# SAMC21_Xplained_Pro_Peripherals.net
KiCad netlist of a schematic drawn in Altium Designer
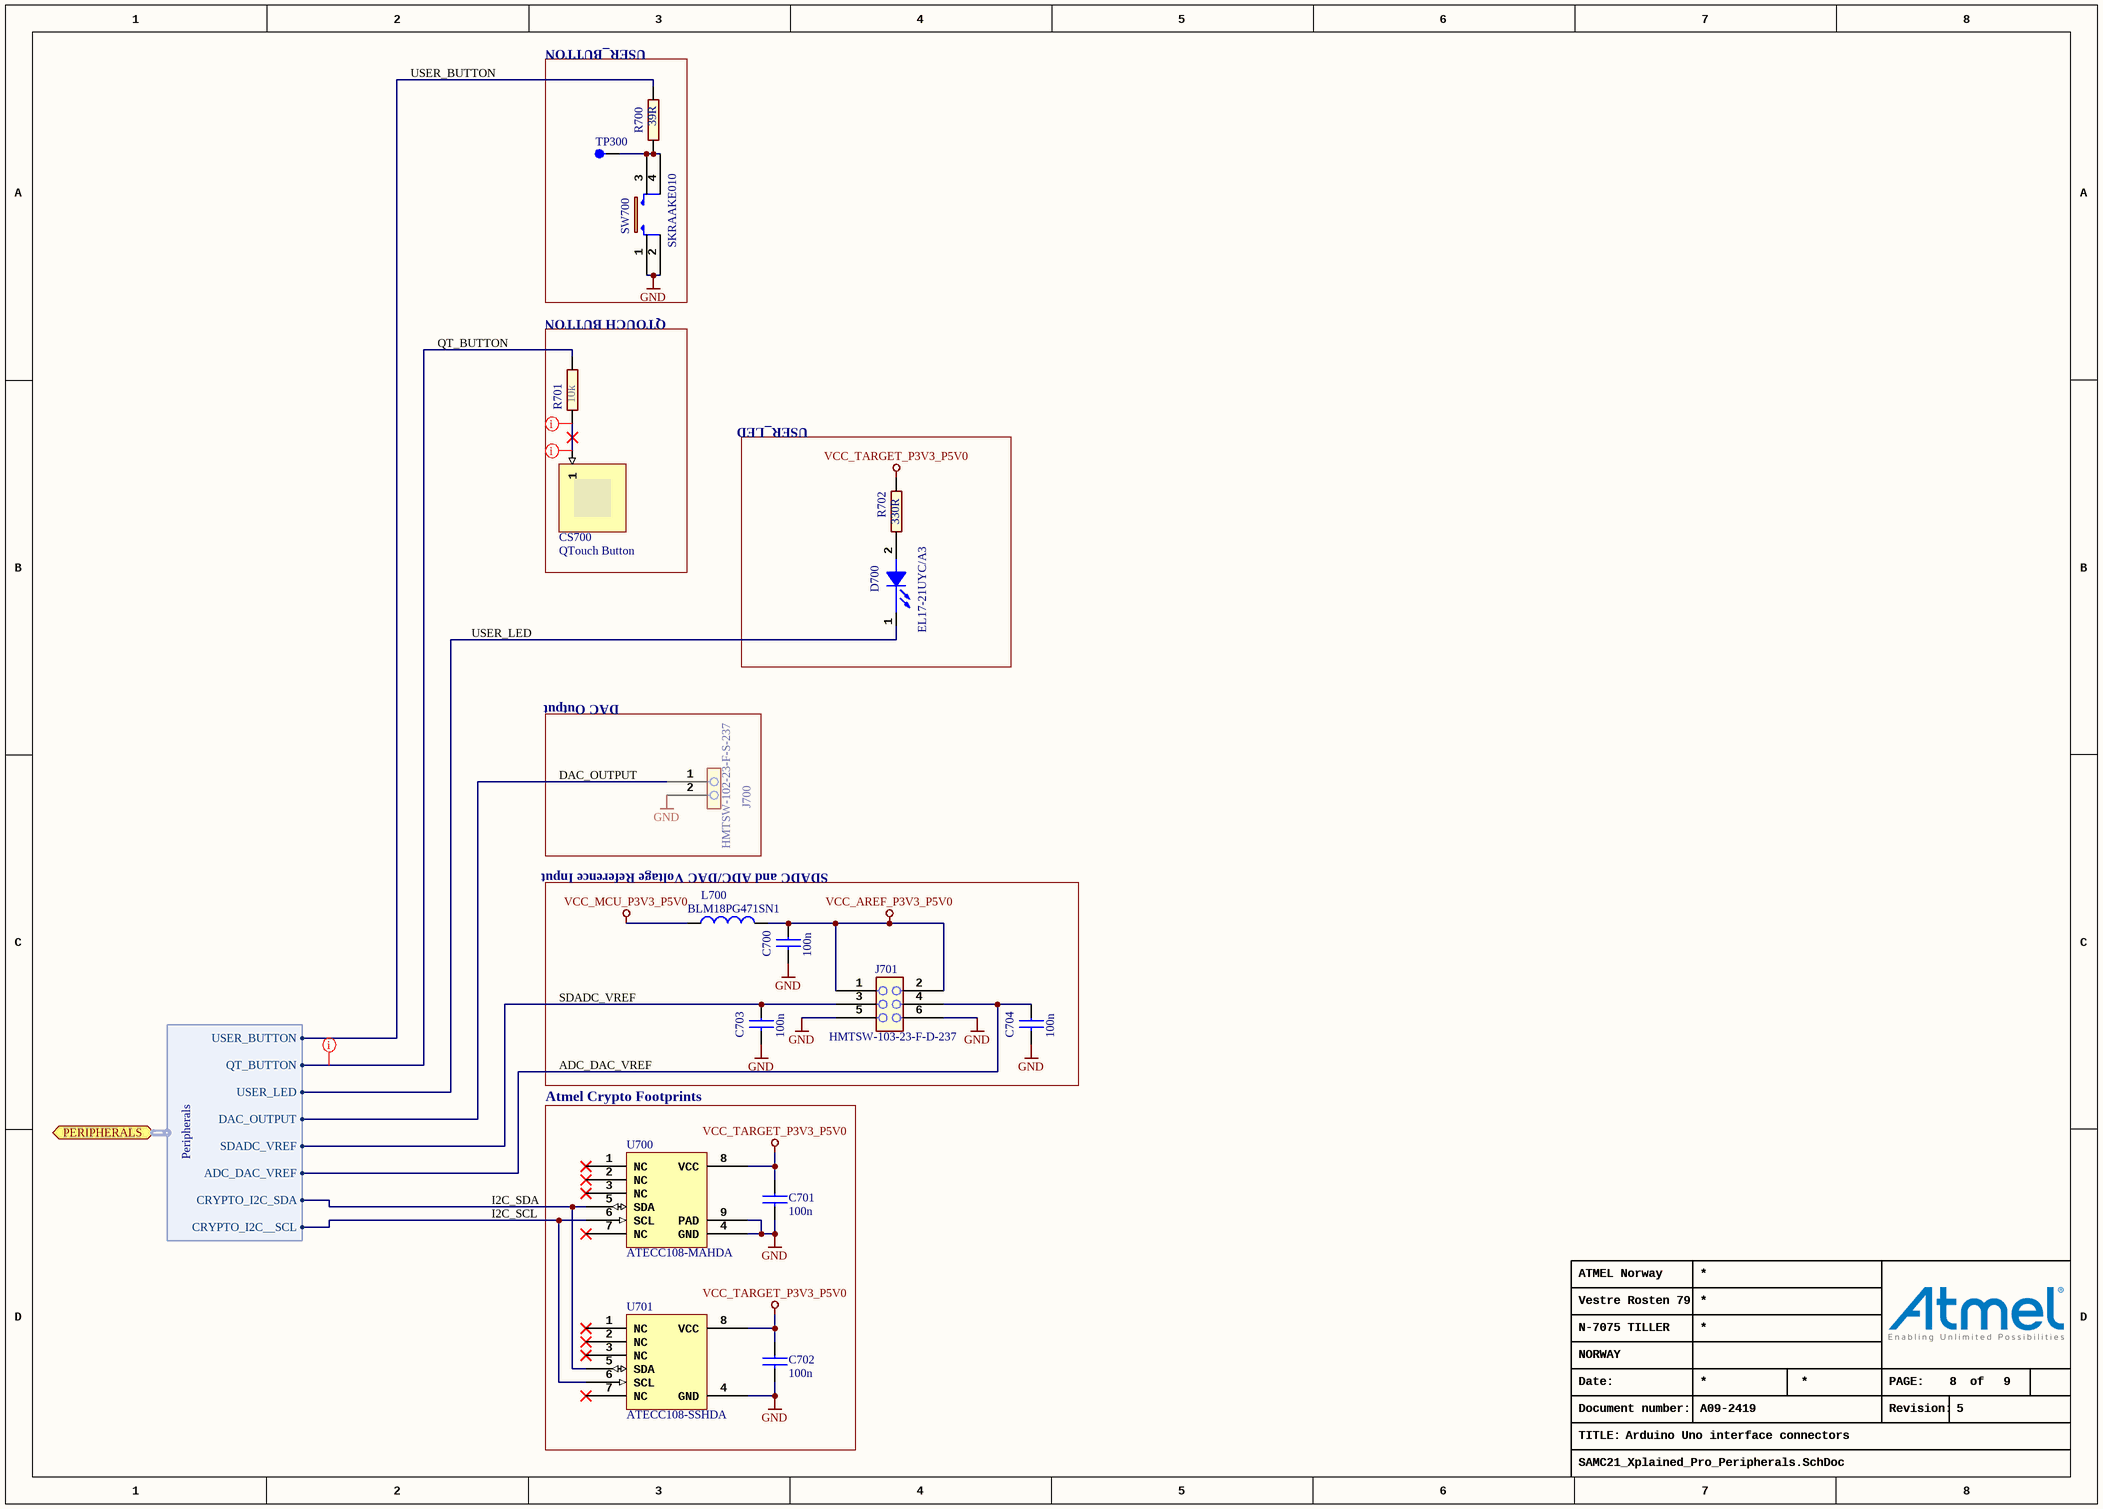
[diagram p0: SAMC21_Xplained_Pro_Peripherals.SchDoc]

(export (version "E")
  (design (tool "Eeschema 10.0.6"))
  (components
    (comp (ref "C700")
      (value "100n")
      (footprint "AP1-00001")
      (description "Ceramic capacitor, SMD 0402, X7R, 16V, +/-10%")
      (fields (field (name "TOLERANCE") "16V, +/-10%") (field (name "MANUFACTURER") "Kemet"))
      (libsource (lib "AltiumDbLib") (part "CAP-NONPOL"))
    )
    (comp (ref "C701")
      (value "100n")
      (footprint "AP1-00001")
      (description "Ceramic capacitor, SMD 0402, X7R, 16V, +/-10%")
      (fields (field (name "TOLERANCE") "16V, +/-10%") (field (name "MANUFACTURER") "Kemet"))
      (libsource (lib "AltiumDbLib") (part "CAP-NONPOL"))
    )
    (comp (ref "C702")
      (value "100n")
      (footprint "AP1-00001")
      (description "Ceramic capacitor, SMD 0402, X7R, 16V, +/-10%")
      (fields (field (name "TOLERANCE") "16V, +/-10%") (field (name "MANUFACTURER") "Kemet"))
      (libsource (lib "AltiumDbLib") (part "CAP-NONPOL"))
    )
    (comp (ref "C703")
      (value "100n")
      (footprint "AP1-00001")
      (description "Ceramic capacitor, SMD 0402, X7R, 16V, +/-10%")
      (fields (field (name "TOLERANCE") "16V, +/-10%") (field (name "MANUFACTURER") "Kemet"))
      (libsource (lib "AltiumDbLib") (part "CAP-NONPOL"))
    )
    (comp (ref "C704")
      (value "100n")
      (footprint "AP1-00001")
      (description "Ceramic capacitor, SMD 0402, X7R, 16V, +/-10%")
      (fields (field (name "TOLERANCE") "16V, +/-10%") (field (name "MANUFACTURER") "Kemet"))
      (libsource (lib "AltiumDbLib") (part "CAP-NONPOL"))
    )
    (comp (ref "CS700") (value "QTouch Button") (libsource (lib "Atmel QTouch") (part "QTouchButton")))
    (comp (ref "D700")
      (value "EL17-21UYC/A3")
      (footprint "AP4-00013")
      (description "LED, Yellow, Wave length=591nm, SMD 0805, ±70°")
      (fields (field (name "MANUFACTURER") "Everlight") (field (name "MPN") "17-21UYC/S530-A3/TR8"))
      (libsource (lib "AltiumDbLib") (part "LED_12"))
    )
    (comp (ref "J700")
      (value "HMTSW-102-23-F-S-237")
      (footprint "AP8-00733")
      (description "1x2 pin header, 2.54mm pitch, Pin-in-Paste THM")
      (fields (field (name "MANUFACTURER") "SAMTEC"))
      (libsource (lib "AltiumDbLib") (part "HEADER 1x2"))
    )
    (comp (ref "J701")
      (value "HMTSW-103-23-F-D-237")
      (footprint "AP8-00182")
      (description "2x3 pin header, 2.54mm pitch, Pin-in-Paste THM")
      (fields (field (name "MANUFACTURER") "SAMTEC"))
      (libsource (lib "AltiumDbLib") (part "HEADER 2x3"))
    )
    (comp (ref "L700")
      (value "BLM18PG471SN1")
      (footprint "AP3-00005")
      (description "SMD RF inductor 0603. Z=470Ohm (@100MHz), Max R(dc)=0.65Ohm, Max current=1A")
      (fields (field (name "TOLERANCE") "±25%") (field (name "MANUFACTURER") "Murata"))
      (libsource (lib "AltiumDbLib") (part "INDUCTOR"))
    )
    (comp (ref "R700")
      (value "39R")
      (footprint "AP2-00000")
      (description "Thick film resistor, SMD 0402, 1/16W, 1%")
      (fields (field (name "TOLERANCE") "1 %"))
      (libsource (lib "") (part "R2_1"))
    )
    (comp (ref "R701")
      (value "10k")
      (footprint "AP2-00000")
      (description "Thick film resistor, SMD 0402, 1/16W, 1%")
      (fields (field (name "TOLERANCE") "1 %") (field (name "MANUFACTURER") "vishay"))
      (libsource (lib "AltiumDbLib") (part "R2"))
    )
    (comp (ref "R702")
      (value "330R")
      (footprint "AP2-00000")
      (description "Thick film resistor, SMD 0402, 1/16W, 1%")
      (fields (field (name "TOLERANCE") "1 %"))
      (libsource (lib "AltiumDbLib") (part "R2"))
    )
    (comp (ref "SW700")
      (value "SKRAAKE010")
      (footprint "AP8-00137")
      (description "6.2x6.2 mm SMD tact switch, same as A08-0091 but less force is needed")
      (fields
        (field (name "MANUFACTURER") "ALPS")
        (field (name "Comment") "same as A08-0091 but less force is needed; Can be ordered in low volumes from Mouser")
      )
      (libsource (lib "AltiumDbLib") (part "PUSHBUTTON1"))
    )
    (comp (ref "TP300")
      (value "~")
      (footprint "AP8-00010")
      (description "Single SMD testpad")
      (libsource (lib "AltiumDbLib") (part "TESTPOINT"))
    )
    (comp (ref "U700")
      (value "ATECC108-MAHDA")
      (footprint "AP6-00409")
      (description "Secure authentication and product validation device, EEPROM, I2C, 2.0 - 5.5V, UDFN8")
      (fields (field (name "MANUFACTURER") "ATMEL") (field (name "MPN") "ATECC108-MAHDA-T"))
      (libsource (lib "AltiumDbLib") (part "ATECC108_UDFN"))
    )
    (comp (ref "U701")
      (value "ATECC108-SSHDA")
      (footprint "AP6-00071")
      (description "Secure authentication and product validation device, EEPROM, I2C, 2.0 - 5.5V, SOIC8")
      (fields (field (name "MANUFACTURER") "ATMEL") (field (name "MPN") "ATECC108-SSHDA-T"))
      (libsource (lib "AltiumDbLib") (part "ATECC108_SOIC"))
    )
  )
  (nets
    (net (code "2") (name "/ADC_DAC_VREF") (class "Default")
      (node (ref "C704") (pin "1") (pinfunction "1_1") (pintype "passive"))
      (node (ref "J701") (pin "4") (pinfunction "4_4") (pintype "passive"))
    )
    (net (code "3") (name "/CRYPTO_I2C_SDA") (class "Default")
      (node (ref "U700") (pin "5") (pinfunction "SDA_5") (pintype "bidirectional"))
      (node (ref "U701") (pin "5") (pinfunction "SDA_5") (pintype "bidirectional"))
    )
    (net (code "4") (name "/CRYPTO_I2C__SCL") (class "Default")
      (node (ref "U700") (pin "6") (pinfunction "SCL_6") (pintype "input"))
      (node (ref "U701") (pin "6") (pinfunction "SCL_6") (pintype "input"))
    )
    (net (code "5") (name "/DAC_OUTPUT") (class "Default")
      (node (ref "J700") (pin "1") (pinfunction "1_1") (pintype "passive"))
    )
    (net (code "6") (name "/QT_BUTTON") (class "Default")
      (node (ref "R701") (pin "2") (pinfunction "2_2") (pintype "passive"))
    )
    (net (code "7") (name "/SDADC_VREF") (class "Default")
      (node (ref "C703") (pin "1") (pinfunction "1_1") (pintype "passive"))
      (node (ref "J701") (pin "3") (pinfunction "3_3") (pintype "passive"))
    )
    (net (code "8") (name "/USER_BUTTON") (class "Default")
      (node (ref "R700") (pin "2") (pinfunction "2_2") (pintype "passive"))
    )
    (net (code "9") (name "/USER_LED") (class "Default")
      (node (ref "D700") (pin "1") (pinfunction "CATHODE_1") (pintype "passive"))
    )
    (net (code "11") (name "GND") (class "Default")
      (node (ref "C700") (pin "2") (pinfunction "2_2") (pintype "passive"))
      (node (ref "C701") (pin "2") (pinfunction "2_2") (pintype "passive"))
      (node (ref "C702") (pin "2") (pinfunction "2_2") (pintype "passive"))
      (node (ref "C703") (pin "2") (pinfunction "2_2") (pintype "passive"))
      (node (ref "C704") (pin "2") (pinfunction "2_2") (pintype "passive"))
      (node (ref "J700") (pin "2") (pinfunction "2_2") (pintype "passive"))
      (node (ref "J701") (pin "5") (pinfunction "5_5") (pintype "passive"))
      (node (ref "J701") (pin "6") (pinfunction "6_6") (pintype "passive"))
      (node (ref "SW700") (pin "1") (pinfunction "1_1") (pintype "passive"))
      (node (ref "SW700") (pin "2") (pinfunction "2_2") (pintype "passive"))
      (node (ref "U700") (pin "4") (pinfunction "GND_4") (pintype "power_in"))
      (node (ref "U700") (pin "9") (pinfunction "PAD_9") (pintype "power_in"))
      (node (ref "U701") (pin "4") (pinfunction "GND_4") (pintype "power_in"))
    )
    (net (code "12") (name "Net-(CS700-Pad1)") (class "Default")
      (node (ref "CS700") (pin "1") (pinfunction "1_1") (pintype "input"))
      (node (ref "R701") (pin "1") (pinfunction "1_1") (pintype "passive"))
    )
    (net (code "13") (name "Net-(D700-ANODE)") (class "Default")
      (node (ref "D700") (pin "2") (pinfunction "ANODE_2") (pintype "passive"))
      (node (ref "R702") (pin "1") (pinfunction "1_1") (pintype "passive"))
    )
    (net (code "14") (name "Net-(R700-Pad1)") (class "Default")
      (node (ref "R700") (pin "1") (pinfunction "1_1") (pintype "passive"))
      (node (ref "SW700") (pin "3") (pinfunction "3_3") (pintype "passive"))
      (node (ref "SW700") (pin "4") (pinfunction "4_4") (pintype "passive"))
      (node (ref "TP300") (pin "1") (pinfunction "1_1") (pintype "passive"))
    )
    (net (code "15") (name "VCC_AREF_P3V3_P5V0") (class "Default")
      (node (ref "C700") (pin "1") (pinfunction "1_1") (pintype "passive"))
      (node (ref "J701") (pin "1") (pinfunction "1_1") (pintype "passive"))
      (node (ref "J701") (pin "2") (pinfunction "2_2") (pintype "passive"))
      (node (ref "L700") (pin "2") (pinfunction "2_2") (pintype "passive"))
    )
    (net (code "16") (name "VCC_MCU_P3V3_P5V0") (class "Default")
      (node (ref "L700") (pin "1") (pinfunction "1_1") (pintype "passive"))
    )
    (net (code "17") (name "VCC_TARGET_P3V3_P5V0") (class "Default")
      (node (ref "C701") (pin "1") (pinfunction "1_1") (pintype "passive"))
      (node (ref "C702") (pin "1") (pinfunction "1_1") (pintype "passive"))
      (node (ref "R702") (pin "2") (pinfunction "2_2") (pintype "passive"))
      (node (ref "U700") (pin "8") (pinfunction "VCC_8") (pintype "power_in"))
      (node (ref "U701") (pin "8") (pinfunction "VCC_8") (pintype "power_in"))
    )
    (net (code "18") (name "unconnected-(U700-NC-Pad1)") (class "Default")
      (node (ref "U700") (pin "1") (pinfunction "NC_1") (pintype "passive+no_connect"))
    )
    (net (code "19") (name "unconnected-(U700-NC-Pad2)") (class "Default")
      (node (ref "U700") (pin "2") (pinfunction "NC_2") (pintype "passive+no_connect"))
    )
    (net (code "20") (name "unconnected-(U700-NC-Pad3)") (class "Default")
      (node (ref "U700") (pin "3") (pinfunction "NC_3") (pintype "passive+no_connect"))
    )
    (net (code "21") (name "unconnected-(U700-NC-Pad7)") (class "Default")
      (node (ref "U700") (pin "7") (pinfunction "NC_7") (pintype "passive+no_connect"))
    )
    (net (code "22") (name "unconnected-(U701-NC-Pad1)") (class "Default")
      (node (ref "U701") (pin "1") (pinfunction "NC_1") (pintype "passive+no_connect"))
    )
    (net (code "23") (name "unconnected-(U701-NC-Pad2)") (class "Default")
      (node (ref "U701") (pin "2") (pinfunction "NC_2") (pintype "passive+no_connect"))
    )
    (net (code "24") (name "unconnected-(U701-NC-Pad3)") (class "Default")
      (node (ref "U701") (pin "3") (pinfunction "NC_3") (pintype "passive+no_connect"))
    )
    (net (code "25") (name "unconnected-(U701-NC-Pad7)") (class "Default")
      (node (ref "U701") (pin "7") (pinfunction "NC_7") (pintype "passive+no_connect"))
    )
  )
)
